# FPGA_Banks_64_65_HR.net
KiCad netlist of a schematic drawn in Altium Designer
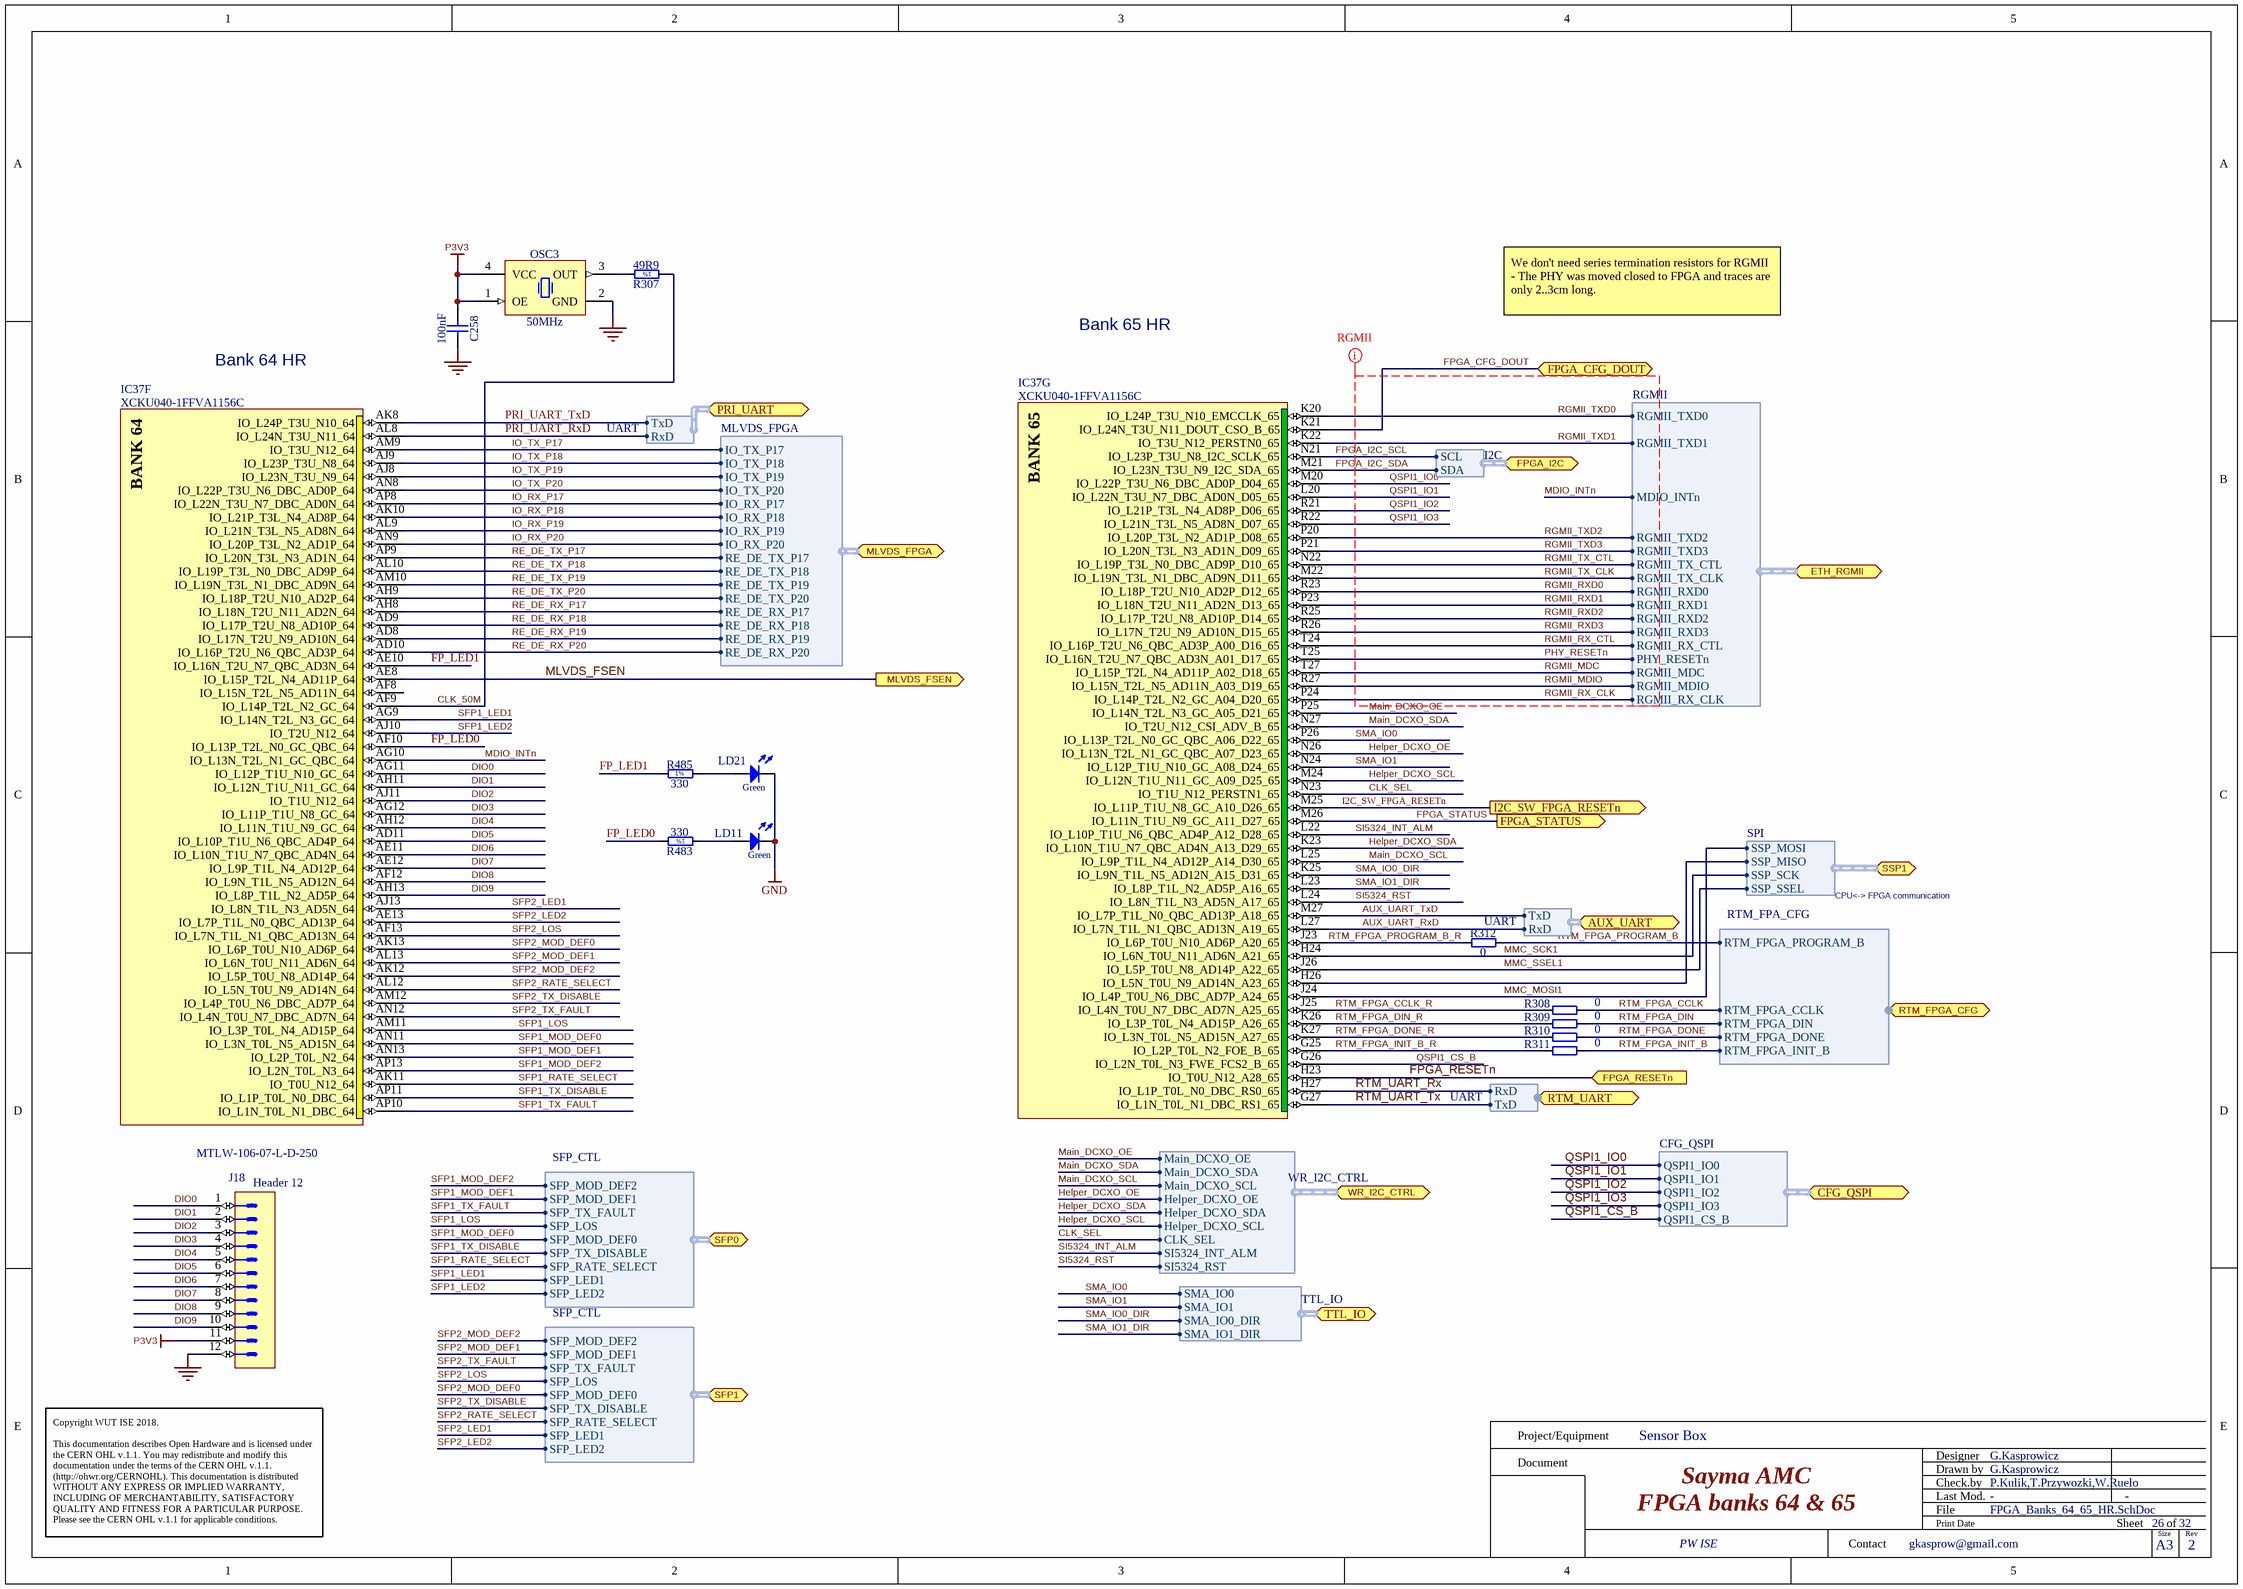
[diagram p0: FPGA_Banks_64_65_HR.SchDoc]

(export (version "E")
  (design (tool "Eeschema 10.0.6"))
  (components
    (comp (ref "C258")
      (value "100nF")
      (footprint "CAPC0603X33N")
      (description "Non-polarised capacitor")
      (fields
        (field (name "MANUFACTURER PART NUMBER") "CC0201_100NF_6.3V_10%_X5R")
        (field (name "MANUFACTURER") "GENERIC")
        (field (name "AUTHOR") "CERN DEM JLC")
      )
      (libsource (lib "Capacitors") (part "Capacitor - non polarized"))
    )
    (comp (ref "IC37")
      (value "XCKU040-1FFVA1156C")
      (footprint "BGA1156C100P34X34_3500X3500X350")
      (description "Kintex UltraScale FPGA, 520 I/O, 530K Cells, 1156-Ball BGA, Speed Grade 1, Commercial Grade")
      (fields (field (name "MANUFACTURER") "XILINX") (field (name "AUTHOR") "CERN DEM CA"))
      (libsource (lib "ICs And Semiconductors") (part "XCKU040-1FFVA1156C"))
    )
    (comp (ref "J18")
      (value "Header 12")
      (footprint "SAMTEC_MTLW-106-07-L-D-250")
      (description "Connector 12 Male")
      (fields
        (field (name "MANUFACTURER PART NUMBER") "MTLW-106-07-L-D-250")
        (field (name "MANUFACTURER") "SAMTEC")
        (field (name "PART NUMBER") "SAMTEC_MTLW-106-07-L-D-250")
        (field (name "AUTHOR") "CERN DEM JLC")
      )
      (libsource (lib "Connectors") (part "Connector 12 Male"))
    )
    (comp (ref "LD11")
      (value "Green")
      (footprint "LED_AVAGO_HSME-C120")
      (description "LED Green 1C 2A")
      (fields
        (field (name "MANUFACTURER PART NUMBER") "HSME-C120")
        (field (name "MANUFACTURER") "AVAGO TECHNOLOGIES")
        (field (name "AUTHOR") "CERN DEM JMW")
      )
      (libsource (lib "ICs And Semiconductors") (part "LED Green 1C 2A"))
    )
    (comp (ref "LD21")
      (value "Green")
      (footprint "LED_KINGBRIGHT_KPH-1608CGCK")
      (description "LED Green 1C 2A")
      (fields
        (field (name "PART NUMBER") "LED_KINGBRIGHT_KPH-1608CGCK")
        (field (name "MANUFACTURER") "KINGBRIGHT")
        (field (name "AUTHOR") "CERN DEM JLC")
      )
      (libsource (lib "ICs And Semiconductors") (part "LED Green 1C 2A"))
    )
    (comp (ref "OSC3")
      (value "50MHz")
      (footprint "OSCSC254P320X500X130-4N")
      (description "Oscillator 4 pins 1=OE 2=GND 3=OUT 4=VCC")
      (fields
        (field (name "MANUFACTURER PART NUMBER") "636L3I050M00000")
        (field (name "MANUFACTURER") "CTS ELECTRONIC COMPONENTS")
        (field (name "AUTHOR") "CERN DEM JMW")
      )
      (libsource (lib "ICs And Semiconductors") (part "Oscillator 1OE 2GND 3OUT 4VCC"))
    )
    (comp (ref "R307")
      (value "49R9")
      (footprint "RESC1005X40N")
      (description "Resistor - 1%")
      (fields
        (field (name "MANUFACTURER PART NUMBER") "R0402_49R9_1%_0.0625W_100PPM")
        (field (name "MANUFACTURER") "GENERIC")
        (field (name "AUTHOR") "CERN DEM JLC")
      )
      (libsource (lib "Resistors") (part "Resistor - 1%"))
    )
    (comp (ref "R308")
      (value "0")
      (footprint "RESC1005X40N")
      (description "Resistor")
      (fields
        (field (name "MANUFACTURER PART NUMBER") "R0402_0R_JUMPER")
        (field (name "MANUFACTURER") "GENERIC")
        (field (name "AUTHOR") "CERN DEM JLC")
      )
      (libsource (lib "Resistors") (part "Resistor"))
    )
    (comp (ref "R309")
      (value "0")
      (footprint "RESC1005X40N")
      (description "Resistor")
      (fields
        (field (name "MANUFACTURER PART NUMBER") "R0402_0R_JUMPER")
        (field (name "MANUFACTURER") "GENERIC")
        (field (name "AUTHOR") "CERN DEM JLC")
      )
      (libsource (lib "Resistors") (part "Resistor"))
    )
    (comp (ref "R310")
      (value "0")
      (footprint "RESC1005X40N")
      (description "Resistor")
      (fields
        (field (name "MANUFACTURER PART NUMBER") "R0402_0R_JUMPER")
        (field (name "MANUFACTURER") "GENERIC")
        (field (name "AUTHOR") "CERN DEM JLC")
      )
      (libsource (lib "Resistors") (part "Resistor"))
    )
    (comp (ref "R311")
      (value "0")
      (footprint "RESC1005X40N")
      (description "Resistor")
      (fields
        (field (name "MANUFACTURER PART NUMBER") "R0402_0R_JUMPER")
        (field (name "MANUFACTURER") "GENERIC")
        (field (name "AUTHOR") "CERN DEM JLC")
      )
      (libsource (lib "Resistors") (part "Resistor"))
    )
    (comp (ref "R312")
      (value "0")
      (footprint "RESC1005X40N")
      (description "Resistor")
      (fields
        (field (name "MANUFACTURER PART NUMBER") "R0402_0R_JUMPER")
        (field (name "MANUFACTURER") "GENERIC")
        (field (name "AUTHOR") "CERN DEM JLC")
      )
      (libsource (lib "Resistors") (part "Resistor"))
    )
    (comp (ref "R483")
      (value "330")
      (footprint "RESC1005X40N")
      (description "Resistor - 1%")
      (fields
        (field (name "MANUFACTURER PART NUMBER") "R0402_330R_1%_0.0625W_100PPM")
        (field (name "MANUFACTURER") "GENERIC")
        (field (name "AUTHOR") "CERN DEM JLC")
      )
      (libsource (lib "Resistors") (part "Resistor - 1%"))
    )
    (comp (ref "R485")
      (value "330")
      (footprint "RESC1005X40N")
      (description "Resistor - 1%")
      (fields
        (field (name "MANUFACTURER PART NUMBER") "R0402_330R_1%_0.0625W_100PPM")
        (field (name "MANUFACTURER") "GENERIC")
        (field (name "AUTHOR") "CERN DEM JLC")
      )
      (libsource (lib "Resistors") (part "Resistor - 1%"))
    )
  )
  (nets
    (net (code "11") (name "/AUX_UART_RxD") (class "Default")
      (node (ref "IC37") (pin "L27") (pinfunction "IO_L7N_T1L_N1_QBC_AD13N_A19_65_L27") (pintype "bidirectional"))
    )
    (net (code "12") (name "/AUX_UART_TxD") (class "Default")
      (node (ref "IC37") (pin "M27") (pinfunction "IO_L7P_T1L_N0_QBC_AD13P_A18_65_M27") (pintype "bidirectional"))
    )
    (net (code "13") (name "/CLK_50M") (class "Default")
      (node (ref "IC37") (pin "AF9") (pinfunction "IO_L14P_T2L_N2_GC_64_AF9") (pintype "bidirectional"))
      (node (ref "R307") (pin "1") (pinfunction "1_1") (pintype "passive"))
    )
    (net (code "14") (name "/CLK_SEL") (class "Default")
      (node (ref "IC37") (pin "N23") (pinfunction "IO_T1U_N12_PERSTN1_65_N23") (pintype "bidirectional"))
    )
    (net (code "15") (name "/DIO0") (class "Default")
      (node (ref "IC37") (pin "AG11") (pinfunction "IO_L12P_T1U_N10_GC_64_AG11") (pintype "bidirectional"))
      (node (ref "J18") (pin "1") (pinfunction "1_1") (pintype "bidirectional"))
    )
    (net (code "16") (name "/DIO1") (class "Default")
      (node (ref "IC37") (pin "AH11") (pinfunction "IO_L12N_T1U_N11_GC_64_AH11") (pintype "bidirectional"))
      (node (ref "J18") (pin "2") (pinfunction "2_2") (pintype "bidirectional"))
    )
    (net (code "17") (name "/DIO2") (class "Default")
      (node (ref "IC37") (pin "AJ11") (pinfunction "IO_T1U_N12_64_AJ11") (pintype "bidirectional"))
      (node (ref "J18") (pin "3") (pinfunction "3_3") (pintype "bidirectional"))
    )
    (net (code "18") (name "/DIO3") (class "Default")
      (node (ref "IC37") (pin "AG12") (pinfunction "IO_L11P_T1U_N8_GC_64_AG12") (pintype "bidirectional"))
      (node (ref "J18") (pin "4") (pinfunction "4_4") (pintype "bidirectional"))
    )
    (net (code "19") (name "/DIO4") (class "Default")
      (node (ref "IC37") (pin "AH12") (pinfunction "IO_L11N_T1U_N9_GC_64_AH12") (pintype "bidirectional"))
      (node (ref "J18") (pin "5") (pinfunction "5_5") (pintype "bidirectional"))
    )
    (net (code "20") (name "/DIO5") (class "Default")
      (node (ref "IC37") (pin "AD11") (pinfunction "IO_L10P_T1U_N6_QBC_AD4P_64_AD11") (pintype "bidirectional"))
      (node (ref "J18") (pin "6") (pinfunction "6_6") (pintype "bidirectional"))
    )
    (net (code "21") (name "/DIO6") (class "Default")
      (node (ref "IC37") (pin "AE11") (pinfunction "IO_L10N_T1U_N7_QBC_AD4N_64_AE11") (pintype "bidirectional"))
      (node (ref "J18") (pin "7") (pinfunction "7_7") (pintype "bidirectional"))
    )
    (net (code "22") (name "/DIO7") (class "Default")
      (node (ref "IC37") (pin "AE12") (pinfunction "IO_L9P_T1L_N4_AD12P_64_AE12") (pintype "bidirectional"))
      (node (ref "J18") (pin "8") (pinfunction "8_8") (pintype "bidirectional"))
    )
    (net (code "23") (name "/DIO8") (class "Default")
      (node (ref "IC37") (pin "AF12") (pinfunction "IO_L9N_T1L_N5_AD12N_64_AF12") (pintype "bidirectional"))
      (node (ref "J18") (pin "9") (pinfunction "9_9") (pintype "bidirectional"))
    )
    (net (code "24") (name "/DIO9") (class "Default")
      (node (ref "IC37") (pin "AH13") (pinfunction "IO_L8P_T1L_N2_AD5P_64_AH13") (pintype "bidirectional"))
      (node (ref "J18") (pin "10") (pinfunction "10_10") (pintype "bidirectional"))
    )
    (net (code "25") (name "/FPGA_CFG_DOUT") (class "Default")
      (node (ref "IC37") (pin "K21") (pinfunction "IO_L24N_T3U_N11_DOUT_CSO_B_65_K21") (pintype "bidirectional"))
    )
    (net (code "26") (name "/FPGA_I2C_SCL") (class "Default")
      (node (ref "IC37") (pin "N21") (pinfunction "IO_L23P_T3U_N8_I2C_SCLK_65_N21") (pintype "bidirectional"))
    )
    (net (code "27") (name "/FPGA_I2C_SDA") (class "Default")
      (node (ref "IC37") (pin "M21") (pinfunction "IO_L23N_T3U_N9_I2C_SDA_65_M21") (pintype "bidirectional"))
    )
    (net (code "28") (name "/FPGA_RESETn") (class "Default")
      (node (ref "IC37") (pin "H23") (pinfunction "IO_T0U_N12_A28_65_H23") (pintype "bidirectional"))
    )
    (net (code "29") (name "/FPGA_STATUS") (class "Default")
      (node (ref "IC37") (pin "M26") (pinfunction "IO_L11N_T1U_N9_GC_A11_D27_65_M26") (pintype "bidirectional"))
    )
    (net (code "30") (name "/FP_LED0") (class "Default")
      (node (ref "IC37") (pin "AF10") (pinfunction "IO_L13P_T2L_N0_GC_QBC_64_AF10") (pintype "bidirectional"))
      (node (ref "R483") (pin "2") (pinfunction "2_2") (pintype "passive"))
    )
    (net (code "31") (name "/FP_LED1") (class "Default")
      (node (ref "IC37") (pin "AE10") (pinfunction "IO_L16N_T2U_N7_QBC_AD3N_64_AE10") (pintype "bidirectional"))
      (node (ref "R485") (pin "1") (pinfunction "1_1") (pintype "passive"))
    )
    (net (code "32") (name "/Helper_DCXO_OE") (class "Default")
      (node (ref "IC37") (pin "N26") (pinfunction "IO_L13N_T2L_N1_GC_QBC_A07_D23_65_N26") (pintype "bidirectional"))
    )
    (net (code "33") (name "/Helper_DCXO_SCL") (class "Default")
      (node (ref "IC37") (pin "M24") (pinfunction "IO_L12N_T1U_N11_GC_A09_D25_65_M24") (pintype "bidirectional"))
    )
    (net (code "34") (name "/Helper_DCXO_SDA") (class "Default")
      (node (ref "IC37") (pin "K23") (pinfunction "IO_L10N_T1U_N7_QBC_AD4N_A13_D29_65_K23") (pintype "bidirectional"))
    )
    (net (code "35") (name "/I2C_SW_FPGA_RESETn") (class "Default")
      (node (ref "IC37") (pin "M25") (pinfunction "IO_L11P_T1U_N8_GC_A10_D26_65_M25") (pintype "bidirectional"))
    )
    (net (code "36") (name "/IO_RX_P17") (class "Default")
      (node (ref "IC37") (pin "AP8") (pinfunction "IO_L22N_T3U_N7_DBC_AD0N_64_AP8") (pintype "bidirectional"))
    )
    (net (code "37") (name "/IO_RX_P18") (class "Default")
      (node (ref "IC37") (pin "AK10") (pinfunction "IO_L21P_T3L_N4_AD8P_64_AK10") (pintype "bidirectional"))
    )
    (net (code "38") (name "/IO_RX_P19") (class "Default")
      (node (ref "IC37") (pin "AL9") (pinfunction "IO_L21N_T3L_N5_AD8N_64_AL9") (pintype "bidirectional"))
    )
    (net (code "39") (name "/IO_RX_P20") (class "Default")
      (node (ref "IC37") (pin "AN9") (pinfunction "IO_L20P_T3L_N2_AD1P_64_AN9") (pintype "bidirectional"))
    )
    (net (code "40") (name "/IO_TX_P17") (class "Default")
      (node (ref "IC37") (pin "AM9") (pinfunction "IO_T3U_N12_64_AM9") (pintype "bidirectional"))
    )
    (net (code "41") (name "/IO_TX_P18") (class "Default")
      (node (ref "IC37") (pin "AJ9") (pinfunction "IO_L23P_T3U_N8_64_AJ9") (pintype "bidirectional"))
    )
    (net (code "42") (name "/IO_TX_P19") (class "Default")
      (node (ref "IC37") (pin "AJ8") (pinfunction "IO_L23N_T3U_N9_64_AJ8") (pintype "bidirectional"))
    )
    (net (code "43") (name "/IO_TX_P20") (class "Default")
      (node (ref "IC37") (pin "AN8") (pinfunction "IO_L22P_T3U_N6_DBC_AD0P_64_AN8") (pintype "bidirectional"))
    )
    (net (code "44") (name "/MDIO_INTn") (class "Default")
      (node (ref "IC37") (pin "AG10") (pinfunction "IO_L13N_T2L_N1_GC_QBC_64_AG10") (pintype "bidirectional"))
    )
    (net (code "45") (name "/MLVDS_FSEN") (class "Default")
      (node (ref "IC37") (pin "AE8") (pinfunction "IO_L15P_T2L_N4_AD11P_64_AE8") (pintype "bidirectional"))
    )
    (net (code "46") (name "/MMC_MOSI1") (class "Default")
      (node (ref "IC37") (pin "J24") (pinfunction "IO_L4P_T0U_N6_DBC_AD7P_A24_65_J24") (pintype "bidirectional"))
    )
    (net (code "47") (name "/MMC_SCK1") (class "Default")
      (node (ref "IC37") (pin "H24") (pinfunction "IO_L6N_T0U_N11_AD6N_A21_65_H24") (pintype "bidirectional"))
    )
    (net (code "48") (name "/MMC_SSEL1") (class "Default")
      (node (ref "IC37") (pin "J26") (pinfunction "IO_L5P_T0U_N8_AD14P_A22_65_J26") (pintype "bidirectional"))
    )
    (net (code "49") (name "/Main_DCXO_OE") (class "Default")
      (node (ref "IC37") (pin "P25") (pinfunction "IO_L14N_T2L_N3_GC_A05_D21_65_P25") (pintype "bidirectional"))
    )
    (net (code "50") (name "/Main_DCXO_SCL") (class "Default")
      (node (ref "IC37") (pin "L25") (pinfunction "IO_L9P_T1L_N4_AD12P_A14_D30_65_L25") (pintype "bidirectional"))
    )
    (net (code "51") (name "/Main_DCXO_SDA") (class "Default")
      (node (ref "IC37") (pin "N27") (pinfunction "IO_T2U_N12_CSI_ADV_B_65_N27") (pintype "bidirectional"))
    )
    (net (code "52") (name "/PHY_RESETn") (class "Default")
      (node (ref "IC37") (pin "T25") (pinfunction "IO_L16N_T2U_N7_QBC_AD3N_A01_D17_65_T25") (pintype "bidirectional"))
    )
    (net (code "53") (name "/PRI_UART_RxD") (class "Default")
      (node (ref "IC37") (pin "AL8") (pinfunction "IO_L24N_T3U_N11_64_AL8") (pintype "bidirectional"))
    )
    (net (code "54") (name "/PRI_UART_TxD") (class "Default")
      (node (ref "IC37") (pin "AK8") (pinfunction "IO_L24P_T3U_N10_64_AK8") (pintype "bidirectional"))
    )
    (net (code "55") (name "/QSPI1_CS_B") (class "Default")
      (node (ref "IC37") (pin "G26") (pinfunction "IO_L2N_T0L_N3_FWE_FCS2_B_65_G26") (pintype "bidirectional"))
    )
    (net (code "56") (name "/QSPI1_IO0") (class "Default")
      (node (ref "IC37") (pin "M20") (pinfunction "IO_L22P_T3U_N6_DBC_AD0P_D04_65_M20") (pintype "bidirectional"))
    )
    (net (code "57") (name "/QSPI1_IO1") (class "Default")
      (node (ref "IC37") (pin "L20") (pinfunction "IO_L22N_T3U_N7_DBC_AD0N_D05_65_L20") (pintype "bidirectional"))
    )
    (net (code "58") (name "/QSPI1_IO2") (class "Default")
      (node (ref "IC37") (pin "R21") (pinfunction "IO_L21P_T3L_N4_AD8P_D06_65_R21") (pintype "bidirectional"))
    )
    (net (code "59") (name "/QSPI1_IO3") (class "Default")
      (node (ref "IC37") (pin "R22") (pinfunction "IO_L21N_T3L_N5_AD8N_D07_65_R22") (pintype "bidirectional"))
    )
    (net (code "60") (name "/RE_DE_RX_P17") (class "Default")
      (node (ref "IC37") (pin "AH8") (pinfunction "IO_L18N_T2U_N11_AD2N_64_AH8") (pintype "bidirectional"))
    )
    (net (code "61") (name "/RE_DE_RX_P18") (class "Default")
      (node (ref "IC37") (pin "AD9") (pinfunction "IO_L17P_T2U_N8_AD10P_64_AD9") (pintype "bidirectional"))
    )
    (net (code "62") (name "/RE_DE_RX_P19") (class "Default")
      (node (ref "IC37") (pin "AD8") (pinfunction "IO_L17N_T2U_N9_AD10N_64_AD8") (pintype "bidirectional"))
    )
    (net (code "63") (name "/RE_DE_RX_P20") (class "Default")
      (node (ref "IC37") (pin "AD10") (pinfunction "IO_L16P_T2U_N6_QBC_AD3P_64_AD10") (pintype "bidirectional"))
    )
    (net (code "64") (name "/RE_DE_TX_P17") (class "Default")
      (node (ref "IC37") (pin "AP9") (pinfunction "IO_L20N_T3L_N3_AD1N_64_AP9") (pintype "bidirectional"))
    )
    (net (code "65") (name "/RE_DE_TX_P18") (class "Default")
      (node (ref "IC37") (pin "AL10") (pinfunction "IO_L19P_T3L_N0_DBC_AD9P_64_AL10") (pintype "bidirectional"))
    )
    (net (code "66") (name "/RE_DE_TX_P19") (class "Default")
      (node (ref "IC37") (pin "AM10") (pinfunction "IO_L19N_T3L_N1_DBC_AD9N_64_AM10") (pintype "bidirectional"))
    )
    (net (code "67") (name "/RE_DE_TX_P20") (class "Default")
      (node (ref "IC37") (pin "AH9") (pinfunction "IO_L18P_T2U_N10_AD2P_64_AH9") (pintype "bidirectional"))
    )
    (net (code "68") (name "/RGMII_MDC") (class "Default")
      (node (ref "IC37") (pin "T27") (pinfunction "IO_L15P_T2L_N4_AD11P_A02_D18_65_T27") (pintype "bidirectional"))
    )
    (net (code "69") (name "/RGMII_MDIO") (class "Default")
      (node (ref "IC37") (pin "R27") (pinfunction "IO_L15N_T2L_N5_AD11N_A03_D19_65_R27") (pintype "bidirectional"))
    )
    (net (code "70") (name "/RGMII_RXD0") (class "Default")
      (node (ref "IC37") (pin "R23") (pinfunction "IO_L18P_T2U_N10_AD2P_D12_65_R23") (pintype "bidirectional"))
    )
    (net (code "71") (name "/RGMII_RXD1") (class "Default")
      (node (ref "IC37") (pin "P23") (pinfunction "IO_L18N_T2U_N11_AD2N_D13_65_P23") (pintype "bidirectional"))
    )
    (net (code "72") (name "/RGMII_RXD2") (class "Default")
      (node (ref "IC37") (pin "R25") (pinfunction "IO_L17P_T2U_N8_AD10P_D14_65_R25") (pintype "bidirectional"))
    )
    (net (code "73") (name "/RGMII_RXD3") (class "Default")
      (node (ref "IC37") (pin "R26") (pinfunction "IO_L17N_T2U_N9_AD10N_D15_65_R26") (pintype "bidirectional"))
    )
    (net (code "74") (name "/RGMII_RX_CLK") (class "Default")
      (node (ref "IC37") (pin "P24") (pinfunction "IO_L14P_T2L_N2_GC_A04_D20_65_P24") (pintype "bidirectional"))
    )
    (net (code "75") (name "/RGMII_RX_CTL") (class "Default")
      (node (ref "IC37") (pin "T24") (pinfunction "IO_L16P_T2U_N6_QBC_AD3P_A00_D16_65_T24") (pintype "bidirectional"))
    )
    (net (code "76") (name "/RGMII_TXD0") (class "Default")
      (node (ref "IC37") (pin "K20") (pinfunction "IO_L24P_T3U_N10_EMCCLK_65_K20") (pintype "bidirectional"))
    )
    (net (code "77") (name "/RGMII_TXD1") (class "Default")
      (node (ref "IC37") (pin "K22") (pinfunction "IO_T3U_N12_PERSTN0_65_K22") (pintype "bidirectional"))
    )
    (net (code "78") (name "/RGMII_TXD2") (class "Default")
      (node (ref "IC37") (pin "P20") (pinfunction "IO_L20P_T3L_N2_AD1P_D08_65_P20") (pintype "bidirectional"))
    )
    (net (code "79") (name "/RGMII_TXD3") (class "Default")
      (node (ref "IC37") (pin "P21") (pinfunction "IO_L20N_T3L_N3_AD1N_D09_65_P21") (pintype "bidirectional"))
    )
    (net (code "80") (name "/RGMII_TX_CLK") (class "Default")
      (node (ref "IC37") (pin "M22") (pinfunction "IO_L19N_T3L_N1_DBC_AD9N_D11_65_M22") (pintype "bidirectional"))
    )
    (net (code "81") (name "/RGMII_TX_CTL") (class "Default")
      (node (ref "IC37") (pin "N22") (pinfunction "IO_L19P_T3L_N0_DBC_AD9P_D10_65_N22") (pintype "bidirectional"))
    )
    (net (code "82") (name "/RTM_FPGA_CCLK") (class "Default")
      (node (ref "R308") (pin "2") (pinfunction "2_2") (pintype "passive"))
    )
    (net (code "83") (name "/RTM_FPGA_CCLK_R") (class "Default")
      (node (ref "IC37") (pin "J25") (pinfunction "IO_L4N_T0U_N7_DBC_AD7N_A25_65_J25") (pintype "bidirectional"))
      (node (ref "R308") (pin "1") (pinfunction "1_1") (pintype "passive"))
    )
    (net (code "84") (name "/RTM_FPGA_DIN") (class "Default")
      (node (ref "R309") (pin "2") (pinfunction "2_2") (pintype "passive"))
    )
    (net (code "85") (name "/RTM_FPGA_DIN_R") (class "Default")
      (node (ref "IC37") (pin "K26") (pinfunction "IO_L3P_T0L_N4_AD15P_A26_65_K26") (pintype "bidirectional"))
      (node (ref "R309") (pin "1") (pinfunction "1_1") (pintype "passive"))
    )
    (net (code "86") (name "/RTM_FPGA_DONE") (class "Default")
      (node (ref "R310") (pin "2") (pinfunction "2_2") (pintype "passive"))
    )
    (net (code "87") (name "/RTM_FPGA_DONE_R") (class "Default")
      (node (ref "IC37") (pin "K27") (pinfunction "IO_L3N_T0L_N5_AD15N_A27_65_K27") (pintype "bidirectional"))
      (node (ref "R310") (pin "1") (pinfunction "1_1") (pintype "passive"))
    )
    (net (code "88") (name "/RTM_FPGA_INIT_B") (class "Default")
      (node (ref "R311") (pin "2") (pinfunction "2_2") (pintype "passive"))
    )
    (net (code "89") (name "/RTM_FPGA_INIT_B_R") (class "Default")
      (node (ref "IC37") (pin "G25") (pinfunction "IO_L2P_T0L_N2_FOE_B_65_G25") (pintype "bidirectional"))
      (node (ref "R311") (pin "1") (pinfunction "1_1") (pintype "passive"))
    )
    (net (code "90") (name "/RTM_FPGA_PROGRAM_B") (class "Default")
      (node (ref "R312") (pin "2") (pinfunction "2_2") (pintype "passive"))
    )
    (net (code "91") (name "/RTM_FPGA_PROGRAM_B_R") (class "Default")
      (node (ref "IC37") (pin "J23") (pinfunction "IO_L6P_T0U_N10_AD6P_A20_65_J23") (pintype "bidirectional"))
      (node (ref "R312") (pin "1") (pinfunction "1_1") (pintype "passive"))
    )
    (net (code "92") (name "/RTM_UART_Rx") (class "Default")
      (node (ref "IC37") (pin "H27") (pinfunction "IO_L1P_T0L_N0_DBC_RS0_65_H27") (pintype "bidirectional"))
    )
    (net (code "93") (name "/RTM_UART_Tx") (class "Default")
      (node (ref "IC37") (pin "G27") (pinfunction "IO_L1N_T0L_N1_DBC_RS1_65_G27") (pintype "bidirectional"))
    )
    (net (code "94") (name "/SFP1_LED1") (class "Default")
      (node (ref "IC37") (pin "AG9") (pinfunction "IO_L14N_T2L_N3_GC_64_AG9") (pintype "bidirectional"))
    )
    (net (code "95") (name "/SFP1_LED2") (class "Default")
      (node (ref "IC37") (pin "AJ10") (pinfunction "IO_T2U_N12_64_AJ10") (pintype "bidirectional"))
    )
    (net (code "96") (name "/SFP1_LOS") (class "Default")
      (node (ref "IC37") (pin "AM11") (pinfunction "IO_L3P_T0L_N4_AD15P_64_AM11") (pintype "bidirectional"))
    )
    (net (code "97") (name "/SFP1_MOD_DEF0") (class "Default")
      (node (ref "IC37") (pin "AN11") (pinfunction "IO_L3N_T0L_N5_AD15N_64_AN11") (pintype "bidirectional"))
    )
    (net (code "98") (name "/SFP1_MOD_DEF1") (class "Default")
      (node (ref "IC37") (pin "AN13") (pinfunction "IO_L2P_T0L_N2_64_AN13") (pintype "bidirectional"))
    )
    (net (code "99") (name "/SFP1_MOD_DEF2") (class "Default")
      (node (ref "IC37") (pin "AP13") (pinfunction "IO_L2N_T0L_N3_64_AP13") (pintype "bidirectional"))
    )
    (net (code "100") (name "/SFP1_RATE_SELECT") (class "Default")
      (node (ref "IC37") (pin "AK11") (pinfunction "IO_T0U_N12_64_AK11") (pintype "bidirectional"))
    )
    (net (code "101") (name "/SFP1_TX_DISABLE") (class "Default")
      (node (ref "IC37") (pin "AP11") (pinfunction "IO_L1P_T0L_N0_DBC_64_AP11") (pintype "bidirectional"))
    )
    (net (code "102") (name "/SFP1_TX_FAULT") (class "Default")
      (node (ref "IC37") (pin "AP10") (pinfunction "IO_L1N_T0L_N1_DBC_64_AP10") (pintype "bidirectional"))
    )
    (net (code "103") (name "/SFP2_LED1") (class "Default")
      (node (ref "IC37") (pin "AJ13") (pinfunction "IO_L8N_T1L_N3_AD5N_64_AJ13") (pintype "bidirectional"))
    )
    (net (code "104") (name "/SFP2_LED2") (class "Default")
      (node (ref "IC37") (pin "AE13") (pinfunction "IO_L7P_T1L_N0_QBC_AD13P_64_AE13") (pintype "bidirectional"))
    )
    (net (code "105") (name "/SFP2_LOS") (class "Default")
      (node (ref "IC37") (pin "AF13") (pinfunction "IO_L7N_T1L_N1_QBC_AD13N_64_AF13") (pintype "bidirectional"))
    )
    (net (code "106") (name "/SFP2_MOD_DEF0") (class "Default")
      (node (ref "IC37") (pin "AK13") (pinfunction "IO_L6P_T0U_N10_AD6P_64_AK13") (pintype "bidirectional"))
    )
    (net (code "107") (name "/SFP2_MOD_DEF1") (class "Default")
      (node (ref "IC37") (pin "AL13") (pinfunction "IO_L6N_T0U_N11_AD6N_64_AL13") (pintype "bidirectional"))
    )
    (net (code "108") (name "/SFP2_MOD_DEF2") (class "Default")
      (node (ref "IC37") (pin "AK12") (pinfunction "IO_L5P_T0U_N8_AD14P_64_AK12") (pintype "bidirectional"))
    )
    (net (code "109") (name "/SFP2_RATE_SELECT") (class "Default")
      (node (ref "IC37") (pin "AL12") (pinfunction "IO_L5N_T0U_N9_AD14N_64_AL12") (pintype "bidirectional"))
    )
    (net (code "110") (name "/SFP2_TX_DISABLE") (class "Default")
      (node (ref "IC37") (pin "AM12") (pinfunction "IO_L4P_T0U_N6_DBC_AD7P_64_AM12") (pintype "bidirectional"))
    )
    (net (code "111") (name "/SFP2_TX_FAULT") (class "Default")
      (node (ref "IC37") (pin "AN12") (pinfunction "IO_L4N_T0U_N7_DBC_AD7N_64_AN12") (pintype "bidirectional"))
    )
    (net (code "112") (name "/SI5324_INT_ALM") (class "Default")
      (node (ref "IC37") (pin "L22") (pinfunction "IO_L10P_T1U_N6_QBC_AD4P_A12_D28_65_L22") (pintype "bidirectional"))
    )
    (net (code "113") (name "/SI5324_RST") (class "Default")
      (node (ref "IC37") (pin "L24") (pinfunction "IO_L8N_T1L_N3_AD5N_A17_65_L24") (pintype "bidirectional"))
    )
    (net (code "114") (name "/SMA_IO0") (class "Default")
      (node (ref "IC37") (pin "P26") (pinfunction "IO_L13P_T2L_N0_GC_QBC_A06_D22_65_P26") (pintype "bidirectional"))
    )
    (net (code "115") (name "/SMA_IO0_DIR") (class "Default")
      (node (ref "IC37") (pin "K25") (pinfunction "IO_L9N_T1L_N5_AD12N_A15_D31_65_K25") (pintype "bidirectional"))
    )
    (net (code "116") (name "/SMA_IO1") (class "Default")
      (node (ref "IC37") (pin "N24") (pinfunction "IO_L12P_T1U_N10_GC_A08_D24_65_N24") (pintype "bidirectional"))
    )
    (net (code "117") (name "/SMA_IO1_DIR") (class "Default")
      (node (ref "IC37") (pin "L23") (pinfunction "IO_L8P_T1L_N2_AD5P_A16_65_L23") (pintype "bidirectional"))
    )
    (net (code "118") (name "/SSP_MISO") (class "Default")
      (node (ref "IC37") (pin "H26") (pinfunction "IO_L5N_T0U_N9_AD14N_A23_65_H26") (pintype "bidirectional"))
    )
    (net (code "129") (name "GND") (class "Default")
      (node (ref "C258") (pin "1") (pinfunction "1_1") (pintype "passive"))
      (node (ref "J18") (pin "12") (pinfunction "12_12") (pintype "bidirectional"))
      (node (ref "LD11") (pin "1") (pinfunction "C_1") (pintype "passive"))
      (node (ref "LD21") (pin "1") (pinfunction "C_1") (pintype "passive"))
      (node (ref "OSC3") (pin "2") (pinfunction "GND_2") (pintype "power_in"))
    )
    (net (code "130") (name "Net-(LD11-A)") (class "Default")
      (node (ref "LD11") (pin "2") (pinfunction "A_2") (pintype "passive"))
      (node (ref "R483") (pin "1") (pinfunction "1_1") (pintype "passive"))
    )
    (net (code "131") (name "Net-(LD21-A)") (class "Default")
      (node (ref "LD21") (pin "2") (pinfunction "A_2") (pintype "passive"))
      (node (ref "R485") (pin "2") (pinfunction "2_2") (pintype "passive"))
    )
    (net (code "132") (name "Net-(OSC3-OUT)") (class "Default")
      (node (ref "OSC3") (pin "3") (pinfunction "OUT_3") (pintype "output"))
      (node (ref "R307") (pin "2") (pinfunction "2_2") (pintype "passive"))
    )
    (net (code "133") (name "P3V3") (class "Default")
      (node (ref "C258") (pin "2") (pinfunction "2_2") (pintype "passive"))
      (node (ref "J18") (pin "11") (pinfunction "11_11") (pintype "bidirectional"))
      (node (ref "OSC3") (pin "1") (pinfunction "OE_1") (pintype "input"))
      (node (ref "OSC3") (pin "4") (pinfunction "VCC_4") (pintype "power_in"))
    )
    (net (code "134") (name "unconnected-(IC37F-IO_L15N_T2L_N5_AD11N_64-PadAF8)") (class "Default")
      (node (ref "IC37") (pin "AF8") (pinfunction "IO_L15N_T2L_N5_AD11N_64_AF8") (pintype "bidirectional"))
    )
  )
)
